# MPPT_MCU.net
KiCad netlist of a schematic drawn in Altium Designer
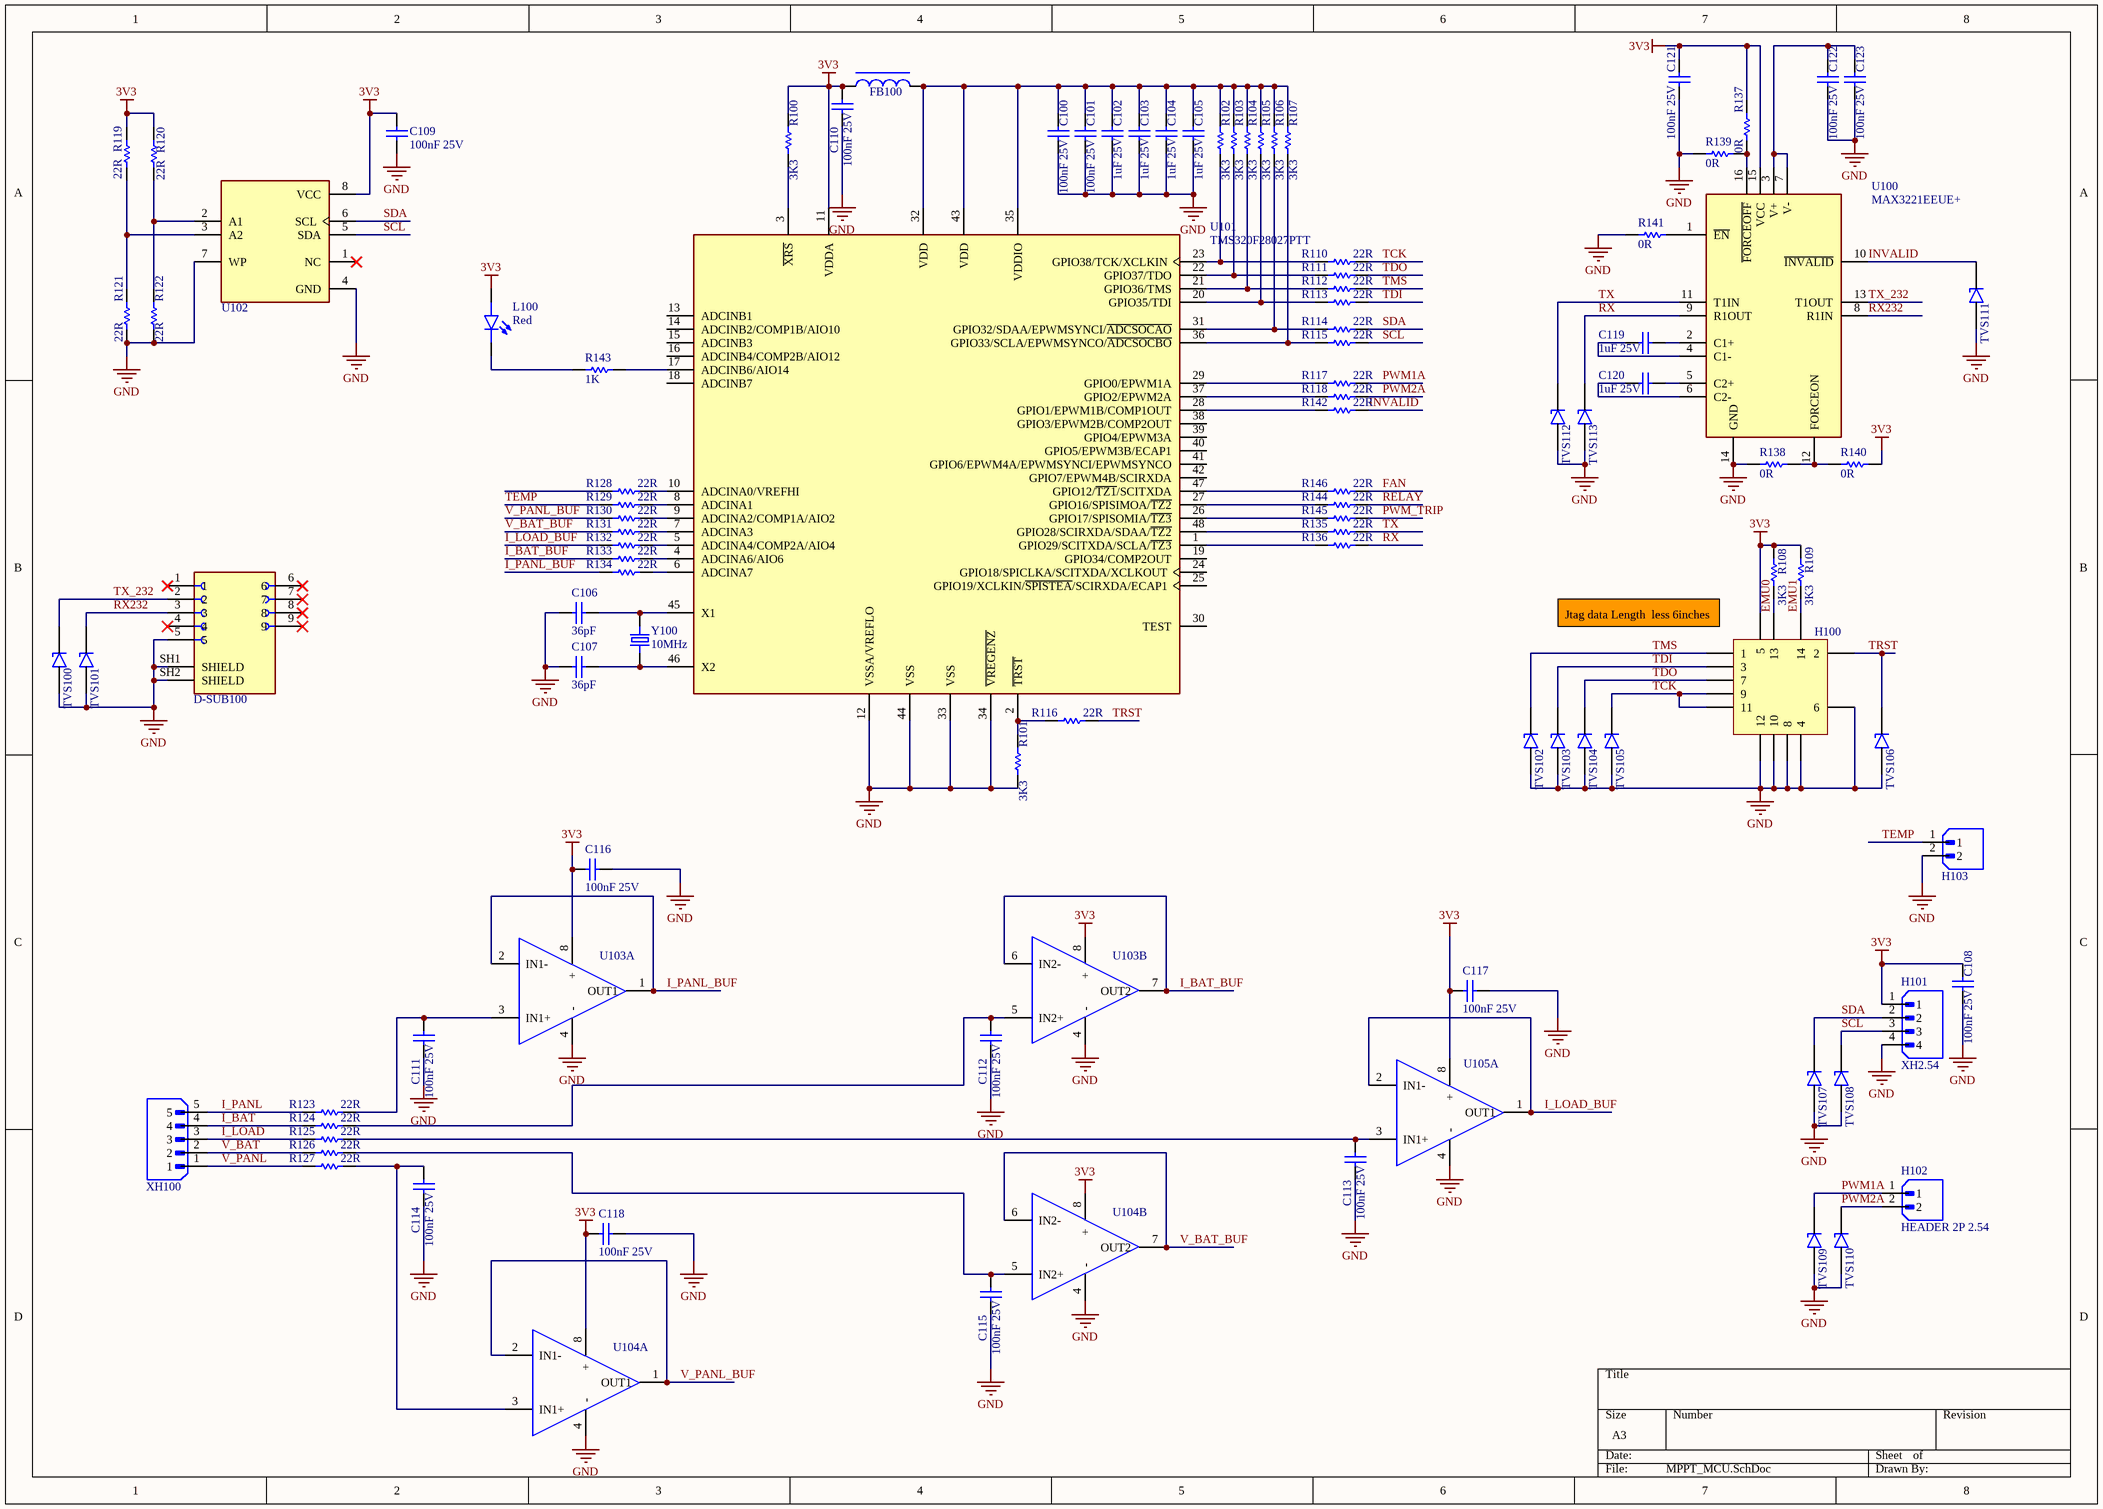
[diagram p0: MPPT_MCU.SchDoc]

(export (version "E")
  (design (tool "Eeschema 10.0.6"))
  (components
    (comp (ref "C100")
      (value "100nF 25V")
      (footprint "Cap cer 0603")
      (description "Multilayer Ceramic Capacitor, 0.1 uF, 25 V, ï¿½ 10%, X7R, 0603 [1608 Metric]")
      (fields
        (field (name "MANUFACTURER") "Murata")
        (field (name "MANUFACTURER PART NUMBER") "GCM188R71E104KA57D")
      )
      (libsource (lib "POWER_PIN_CAMERA") (part "GCM188R71E104KA57D"))
    )
    (comp (ref "C101")
      (value "100nF 25V")
      (footprint "Cap cer 0603")
      (description "Multilayer Ceramic Capacitor, 0.1 uF, 25 V, ï¿½ 10%, X7R, 0603 [1608 Metric]")
      (fields
        (field (name "MANUFACTURER") "Murata")
        (field (name "MANUFACTURER PART NUMBER") "GCM188R71E104KA57D")
      )
      (libsource (lib "POWER_PIN_CAMERA") (part "GCM188R71E104KA57D"))
    )
    (comp (ref "C102")
      (value "1uF 25V")
      (footprint "Cap cer 0603")
      (fields
        (field (name "MANUFACTURER") "Murata")
        (field (name "MANUFACTURER PART NUMBER") "GCM188R71E105KA64J")
        (field (name "TOLERANCE") "10%")
      )
      (libsource (lib "POWER_PIN_CAMERA") (part "GCM188R71E105KA64J"))
    )
    (comp (ref "C103")
      (value "1uF 25V")
      (footprint "Cap cer 0603")
      (fields
        (field (name "MANUFACTURER") "Murata")
        (field (name "MANUFACTURER PART NUMBER") "GCM188R71E105KA64J")
        (field (name "TOLERANCE") "10%")
      )
      (libsource (lib "POWER_PIN_CAMERA") (part "GCM188R71E105KA64J"))
    )
    (comp (ref "C104")
      (value "1uF 25V")
      (footprint "Cap cer 0603")
      (fields
        (field (name "MANUFACTURER") "Murata")
        (field (name "MANUFACTURER PART NUMBER") "GCM188R71E105KA64J")
        (field (name "TOLERANCE") "10%")
      )
      (libsource (lib "POWER_PIN_CAMERA") (part "GCM188R71E105KA64J"))
    )
    (comp (ref "C105")
      (value "1uF 25V")
      (footprint "Cap cer 0603")
      (fields
        (field (name "MANUFACTURER") "Murata")
        (field (name "MANUFACTURER PART NUMBER") "GCM188R71E105KA64J")
        (field (name "TOLERANCE") "10%")
      )
      (libsource (lib "POWER_PIN_CAMERA") (part "GCM188R71E105KA64J"))
    )
    (comp (ref "C106")
      (value "36pF")
      (footprint "Cap cer 0603")
      (description "Cap Ceramic 36pF 50V C0G 5% SMD 0603 125C T/R")
      (fields
        (field (name "MANUFACTURER") "Murata")
        (field (name "MANUFACTURER PART NUMBER") "GRM1885C1H360JA01D")
      )
      (libsource (lib "POWER_PIN_CAMERA") (part "GRM1885C1H360JA01D"))
    )
    (comp (ref "C107")
      (value "36pF")
      (footprint "Cap cer 0603")
      (description "Cap Ceramic 36pF 50V C0G 5% SMD 0603 125C T/R")
      (fields
        (field (name "MANUFACTURER") "Murata")
        (field (name "MANUFACTURER PART NUMBER") "GRM1885C1H360JA01D")
      )
      (libsource (lib "POWER_PIN_CAMERA") (part "GRM1885C1H360JA01D"))
    )
    (comp (ref "C108")
      (value "100nF 25V")
      (footprint "Cap cer 0603")
      (description "Multilayer Ceramic Capacitor, 0.1 uF, 25 V, ï¿½ 10%, X7R, 0603 [1608 Metric]")
      (fields
        (field (name "MANUFACTURER") "Murata")
        (field (name "MANUFACTURER PART NUMBER") "GCM188R71E104KA57D")
      )
      (libsource (lib "POWER_PIN_CAMERA") (part "GCM188R71E104KA57D"))
    )
    (comp (ref "C109")
      (value "100nF 25V")
      (footprint "Cap cer 0603")
      (description "Multilayer Ceramic Capacitor, 0.1 uF, 25 V, ï¿½ 10%, X7R, 0603 [1608 Metric]")
      (fields
        (field (name "MANUFACTURER") "Murata")
        (field (name "MANUFACTURER PART NUMBER") "GCM188R71E104KA57D")
      )
      (libsource (lib "POWER_PIN_CAMERA") (part "GCM188R71E104KA57D"))
    )
    (comp (ref "C110")
      (value "100nF 25V")
      (footprint "Cap cer 0603")
      (description "Multilayer Ceramic Capacitor, 0.1 uF, 25 V, ï¿½ 10%, X7R, 0603 [1608 Metric]")
      (fields
        (field (name "MANUFACTURER") "Murata")
        (field (name "MANUFACTURER PART NUMBER") "GCM188R71E104KA57D")
      )
      (libsource (lib "POWER_PIN_CAMERA") (part "GCM188R71E104KA57D"))
    )
    (comp (ref "C111")
      (value "100nF 25V")
      (footprint "Cap cer 0603")
      (description "Multilayer Ceramic Capacitor, 0.1 uF, 25 V, ï¿½ 10%, X7R, 0603 [1608 Metric]")
      (fields
        (field (name "MANUFACTURER") "Murata")
        (field (name "MANUFACTURER PART NUMBER") "GCM188R71E104KA57D")
      )
      (libsource (lib "POWER_PIN_CAMERA") (part "GCM188R71E104KA57D"))
    )
    (comp (ref "C112")
      (value "100nF 25V")
      (footprint "Cap cer 0603")
      (description "Multilayer Ceramic Capacitor, 0.1 uF, 25 V, ï¿½ 10%, X7R, 0603 [1608 Metric]")
      (fields
        (field (name "MANUFACTURER") "Murata")
        (field (name "MANUFACTURER PART NUMBER") "GCM188R71E104KA57D")
      )
      (libsource (lib "POWER_PIN_CAMERA") (part "GCM188R71E104KA57D"))
    )
    (comp (ref "C113")
      (value "100nF 25V")
      (footprint "Cap cer 0603")
      (description "Multilayer Ceramic Capacitor, 0.1 uF, 25 V, ï¿½ 10%, X7R, 0603 [1608 Metric]")
      (fields
        (field (name "MANUFACTURER") "Murata")
        (field (name "MANUFACTURER PART NUMBER") "GCM188R71E104KA57D")
      )
      (libsource (lib "POWER_PIN_CAMERA") (part "GCM188R71E104KA57D"))
    )
    (comp (ref "C114")
      (value "100nF 25V")
      (footprint "Cap cer 0603")
      (description "Multilayer Ceramic Capacitor, 0.1 uF, 25 V, ï¿½ 10%, X7R, 0603 [1608 Metric]")
      (fields
        (field (name "MANUFACTURER") "Murata")
        (field (name "MANUFACTURER PART NUMBER") "GCM188R71E104KA57D")
      )
      (libsource (lib "POWER_PIN_CAMERA") (part "GCM188R71E104KA57D"))
    )
    (comp (ref "C115")
      (value "100nF 25V")
      (footprint "Cap cer 0603")
      (description "Multilayer Ceramic Capacitor, 0.1 uF, 25 V, ï¿½ 10%, X7R, 0603 [1608 Metric]")
      (fields
        (field (name "MANUFACTURER") "Murata")
        (field (name "MANUFACTURER PART NUMBER") "GCM188R71E104KA57D")
      )
      (libsource (lib "POWER_PIN_CAMERA") (part "GCM188R71E104KA57D"))
    )
    (comp (ref "C116")
      (value "100nF 25V")
      (footprint "Cap cer 0603")
      (description "Multilayer Ceramic Capacitor, 0.1 uF, 25 V, ï¿½ 10%, X7R, 0603 [1608 Metric]")
      (fields
        (field (name "MANUFACTURER") "Murata")
        (field (name "MANUFACTURER PART NUMBER") "GCM188R71E104KA57D")
      )
      (libsource (lib "POWER_PIN_CAMERA") (part "GCM188R71E104KA57D"))
    )
    (comp (ref "C117")
      (value "100nF 25V")
      (footprint "Cap cer 0603")
      (description "Multilayer Ceramic Capacitor, 0.1 uF, 25 V, ï¿½ 10%, X7R, 0603 [1608 Metric]")
      (fields
        (field (name "MANUFACTURER") "Murata")
        (field (name "MANUFACTURER PART NUMBER") "GCM188R71E104KA57D")
      )
      (libsource (lib "POWER_PIN_CAMERA") (part "GCM188R71E104KA57D"))
    )
    (comp (ref "C118")
      (value "100nF 25V")
      (footprint "Cap cer 0603")
      (description "Multilayer Ceramic Capacitor, 0.1 uF, 25 V, ï¿½ 10%, X7R, 0603 [1608 Metric]")
      (fields
        (field (name "MANUFACTURER") "Murata")
        (field (name "MANUFACTURER PART NUMBER") "GCM188R71E104KA57D")
      )
      (libsource (lib "POWER_PIN_CAMERA") (part "GCM188R71E104KA57D"))
    )
    (comp (ref "C119")
      (value "1uF 25V")
      (footprint "Cap cer 0603")
      (fields
        (field (name "MANUFACTURER") "Murata")
        (field (name "MANUFACTURER PART NUMBER") "GCM188R71E105KA64J")
        (field (name "TOLERANCE") "10%")
      )
      (libsource (lib "POWER_PIN_CAMERA") (part "GCM188R71E105KA64J"))
    )
    (comp (ref "C120")
      (value "1uF 25V")
      (footprint "Cap cer 0603")
      (fields
        (field (name "MANUFACTURER") "Murata")
        (field (name "MANUFACTURER PART NUMBER") "GCM188R71E105KA64J")
        (field (name "TOLERANCE") "10%")
      )
      (libsource (lib "POWER_PIN_CAMERA") (part "GCM188R71E105KA64J"))
    )
    (comp (ref "C121")
      (value "100nF 25V")
      (footprint "Cap cer 0603")
      (description "Multilayer Ceramic Capacitor, 0.1 uF, 25 V, ï¿½ 10%, X7R, 0603 [1608 Metric]")
      (fields
        (field (name "MANUFACTURER") "Murata")
        (field (name "MANUFACTURER PART NUMBER") "GCM188R71E104KA57D")
      )
      (libsource (lib "POWER_PIN_CAMERA") (part "GCM188R71E104KA57D"))
    )
    (comp (ref "C122")
      (value "100nF 25V")
      (footprint "Cap cer 0603")
      (description "Multilayer Ceramic Capacitor, 0.1 uF, 25 V, ï¿½ 10%, X7R, 0603 [1608 Metric]")
      (fields
        (field (name "MANUFACTURER") "Murata")
        (field (name "MANUFACTURER PART NUMBER") "GCM188R71E104KA57D")
      )
      (libsource (lib "POWER_PIN_CAMERA") (part "GCM188R71E104KA57D"))
    )
    (comp (ref "C123")
      (value "100nF 25V")
      (footprint "Cap cer 0603")
      (description "Multilayer Ceramic Capacitor, 0.1 uF, 25 V, ï¿½ 10%, X7R, 0603 [1608 Metric]")
      (fields
        (field (name "MANUFACTURER") "Murata")
        (field (name "MANUFACTURER PART NUMBER") "GCM188R71E104KA57D")
      )
      (libsource (lib "POWER_PIN_CAMERA") (part "GCM188R71E104KA57D"))
    )
    (comp (ref "D-SUB100")
      (value "9PIN")
      (footprint "D-SUB")
      (description "Conn D-Subminiature SKT 9 POS 2.74mm Solder RA Thru-Hole 9 Terminal 1 Port Tray")
      (fields
        (field (name "MANUFACTURER") "TE Connectivity AMP")
        (field (name "MANUFACTURER PART NUMBER") "5747844-6")
      )
      (libsource (lib "MPPT_600W") (part "5747844-6"))
    )
    (comp (ref "FB100")
      (value "Ferrite Beads Multi-Layer 390Ohm 25% 100MHz 500mA 300mOhm DCR 0603 Automotive T/R")
      (footprint "FERRITE BEAD 0603")
      (fields
        (field (name "MANUFACTURER") "Murata")
        (field (name "MANUFACTURER PART NUMBER") "BLM18EG391TH1D")
        (field (name "TOLERANCE") "25%")
      )
      (libsource (lib "MPPT_600W") (part "Ferrite Bead"))
    )
    (comp (ref "H100")
      (value "HDR2X7 2.54mm")
      (footprint "HDR2X7")
      (libsource (lib "MPPT_600W") (part "HDR2X7"))
    )
    (comp (ref "H101")
      (value "XH2.54")
      (footprint "XH2.54")
      (description "Board Connector, 4 Contact(s), 1 Row(s), Male, Straight, Solder Terminal,")
      (fields (field (name "MANUFACTURER") "JST") (field (name "MANUFACTURER PART NUMBER") "B4B-XH-A"))
      (libsource (lib "POWER_PIN_CAMERA") (part "B4B-XH-A"))
    )
    (comp (ref "H102")
      (value "HEADER 2P 2.54")
      (footprint "HEADER 2P 2.544")
      (description "CONNECTOR HEADER, XH SERIES, 2 POSITION, 2.50MM, Press-Fit Solder, Detent Lock, Natural")
      (fields
        (field (name "MANUFACTURER") "JST")
        (field (name "MANUFACTURER PART NUMBER") "B2B-XH-A(LF)(SN)")
      )
      (libsource (lib "MPPT_600W") (part "B2B-XH-A(LF)(SN)"))
    )
    (comp (ref "H103")
      (value "HEADER 2P 2.54")
      (footprint "HEADER 2P 2.544")
      (description "CONNECTOR HEADER, XH SERIES, 2 POSITION, 2.50MM, Press-Fit Solder, Detent Lock, Natural")
      (fields
        (field (name "MANUFACTURER") "JST")
        (field (name "MANUFACTURER PART NUMBER") "B2B-XH-A(LF)(SN)")
      )
      (libsource (lib "MPPT_600W") (part "B2B-XH-A(LF)(SN)"))
    )
    (comp (ref "L100")
      (value "Red")
      (footprint "Led 0603")
      (description "LED Uni-Color Red 2-Pin Chip 0603(1608Metric) T/R")
      (fields
        (field (name "MANUFACTURER") "Dialight")
        (field (name "MANUFACTURER PART NUMBER") "597-5004-407F")
      )
      (libsource (lib "POWER_PIN_CAMERA") (part "597-5004-407F"))
    )
    (comp (ref "R100")
      (value "3K3")
      (footprint "Res 0603")
      (description "Res Thick Film 0603 10K Ohm 5% 1/10W ¦200ppm/¦C SMD Paper T/R")
      (fields
        (field (name "MANUFACTURER") "Vishay Dale")
        (field (name "MANUFACTURER PART NUMBER") "CRCW060310K0JNEA")
      )
      (libsource (lib "POWER_PIN_CAMERA") (part "Resistor 10K"))
    )
    (comp (ref "R101")
      (value "3K3")
      (footprint "Res 0603")
      (description "Res Thick Film 0603 10K Ohm 5% 1/10W ¦200ppm/¦C SMD Paper T/R")
      (fields
        (field (name "MANUFACTURER") "Vishay Dale")
        (field (name "MANUFACTURER PART NUMBER") "CRCW060310K0JNEA")
      )
      (libsource (lib "POWER_PIN_CAMERA") (part "Resistor 10K"))
    )
    (comp (ref "R102")
      (value "3K3")
      (footprint "Res 0603")
      (description "Res Thick Film 0603 10K Ohm 5% 1/10W ¦200ppm/¦C SMD Paper T/R")
      (fields
        (field (name "MANUFACTURER") "Vishay Dale")
        (field (name "MANUFACTURER PART NUMBER") "CRCW060310K0JNEA")
      )
      (libsource (lib "POWER_PIN_CAMERA") (part "Resistor 10K"))
    )
    (comp (ref "R103")
      (value "3K3")
      (footprint "Res 0603")
      (description "Res Thick Film 0603 10K Ohm 5% 1/10W ¦200ppm/¦C SMD Paper T/R")
      (fields
        (field (name "MANUFACTURER") "Vishay Dale")
        (field (name "MANUFACTURER PART NUMBER") "CRCW060310K0JNEA")
      )
      (libsource (lib "POWER_PIN_CAMERA") (part "Resistor 10K"))
    )
    (comp (ref "R104")
      (value "3K3")
      (footprint "Res 0603")
      (description "Res Thick Film 0603 10K Ohm 5% 1/10W ¦200ppm/¦C SMD Paper T/R")
      (fields
        (field (name "MANUFACTURER") "Vishay Dale")
        (field (name "MANUFACTURER PART NUMBER") "CRCW060310K0JNEA")
      )
      (libsource (lib "POWER_PIN_CAMERA") (part "Resistor 10K"))
    )
    (comp (ref "R105")
      (value "3K3")
      (footprint "Res 0603")
      (description "Res Thick Film 0603 10K Ohm 5% 1/10W ¦200ppm/¦C SMD Paper T/R")
      (fields
        (field (name "MANUFACTURER") "Vishay Dale")
        (field (name "MANUFACTURER PART NUMBER") "CRCW060310K0JNEA")
      )
      (libsource (lib "POWER_PIN_CAMERA") (part "Resistor 10K"))
    )
    (comp (ref "R106")
      (value "3K3")
      (footprint "Res 0603")
      (description "Res Thick Film 0603 10K Ohm 5% 1/10W ¦200ppm/¦C SMD Paper T/R")
      (fields
        (field (name "MANUFACTURER") "Vishay Dale")
        (field (name "MANUFACTURER PART NUMBER") "CRCW060310K0JNEA")
      )
      (libsource (lib "POWER_PIN_CAMERA") (part "Resistor 10K"))
    )
    (comp (ref "R107")
      (value "3K3")
      (footprint "Res 0603")
      (description "Res Thick Film 0603 10K Ohm 5% 1/10W ¦200ppm/¦C SMD Paper T/R")
      (fields
        (field (name "MANUFACTURER") "Vishay Dale")
        (field (name "MANUFACTURER PART NUMBER") "CRCW060310K0JNEA")
      )
      (libsource (lib "POWER_PIN_CAMERA") (part "Resistor 10K"))
    )
    (comp (ref "R108")
      (value "3K3")
      (footprint "Res 0603")
      (description "Res Thick Film 0603 10K Ohm 5% 1/10W ¦200ppm/¦C SMD Paper T/R")
      (fields
        (field (name "MANUFACTURER") "Vishay Dale")
        (field (name "MANUFACTURER PART NUMBER") "CRCW060310K0JNEA")
      )
      (libsource (lib "POWER_PIN_CAMERA") (part "Resistor 10K"))
    )
    (comp (ref "R109")
      (value "3K3")
      (footprint "Res 0603")
      (description "Res Thick Film 0603 10K Ohm 5% 1/10W ¦200ppm/¦C SMD Paper T/R")
      (fields
        (field (name "MANUFACTURER") "Vishay Dale")
        (field (name "MANUFACTURER PART NUMBER") "CRCW060310K0JNEA")
      )
      (libsource (lib "POWER_PIN_CAMERA") (part "Resistor 10K"))
    )
    (comp (ref "R110")
      (value "22R")
      (footprint "Res 0603")
      (description "Res Thick Film 0603 22 Ohm 5% 1/10W ±200ppm/°C Molded SMD SMD Paper Tape on Plastic Reel")
      (fields
        (field (name "MANUFACTURER") "Bourns")
        (field (name "MANUFACTURER PART NUMBER") "CR0603-JW-220ELF")
      )
      (libsource (lib "POWER_PIN_CAMERA") (part "Resistor 22R"))
    )
    (comp (ref "R111")
      (value "22R")
      (footprint "Res 0603")
      (description "Res Thick Film 0603 22 Ohm 5% 1/10W ±200ppm/°C Molded SMD SMD Paper Tape on Plastic Reel")
      (fields
        (field (name "MANUFACTURER") "Bourns")
        (field (name "MANUFACTURER PART NUMBER") "CR0603-JW-220ELF")
      )
      (libsource (lib "POWER_PIN_CAMERA") (part "Resistor 22R"))
    )
    (comp (ref "R112")
      (value "22R")
      (footprint "Res 0603")
      (description "Res Thick Film 0603 22 Ohm 5% 1/10W ±200ppm/°C Molded SMD SMD Paper Tape on Plastic Reel")
      (fields
        (field (name "MANUFACTURER") "Bourns")
        (field (name "MANUFACTURER PART NUMBER") "CR0603-JW-220ELF")
      )
      (libsource (lib "POWER_PIN_CAMERA") (part "Resistor 22R"))
    )
    (comp (ref "R113")
      (value "22R")
      (footprint "Res 0603")
      (description "Res Thick Film 0603 22 Ohm 5% 1/10W ±200ppm/°C Molded SMD SMD Paper Tape on Plastic Reel")
      (fields
        (field (name "MANUFACTURER") "Bourns")
        (field (name "MANUFACTURER PART NUMBER") "CR0603-JW-220ELF")
      )
      (libsource (lib "POWER_PIN_CAMERA") (part "Resistor 22R"))
    )
    (comp (ref "R114")
      (value "22R")
      (footprint "Res 0603")
      (description "Res Thick Film 0603 22 Ohm 5% 1/10W ±200ppm/°C Molded SMD SMD Paper Tape on Plastic Reel")
      (fields
        (field (name "MANUFACTURER") "Bourns")
        (field (name "MANUFACTURER PART NUMBER") "CR0603-JW-220ELF")
      )
      (libsource (lib "POWER_PIN_CAMERA") (part "Resistor 22R"))
    )
    (comp (ref "R115")
      (value "22R")
      (footprint "Res 0603")
      (description "Res Thick Film 0603 22 Ohm 5% 1/10W ±200ppm/°C Molded SMD SMD Paper Tape on Plastic Reel")
      (fields
        (field (name "MANUFACTURER") "Bourns")
        (field (name "MANUFACTURER PART NUMBER") "CR0603-JW-220ELF")
      )
      (libsource (lib "POWER_PIN_CAMERA") (part "Resistor 22R"))
    )
    (comp (ref "R116")
      (value "22R")
      (footprint "Res 0603")
      (description "Res Thick Film 0603 22 Ohm 5% 1/10W ±200ppm/°C Molded SMD SMD Paper Tape on Plastic Reel")
      (fields
        (field (name "MANUFACTURER") "Bourns")
        (field (name "MANUFACTURER PART NUMBER") "CR0603-JW-220ELF")
      )
      (libsource (lib "POWER_PIN_CAMERA") (part "Resistor 22R"))
    )
    (comp (ref "R117")
      (value "22R")
      (footprint "Res 0603")
      (description "Res Thick Film 0603 22 Ohm 5% 1/10W ±200ppm/°C Molded SMD SMD Paper Tape on Plastic Reel")
      (fields
        (field (name "MANUFACTURER") "Bourns")
        (field (name "MANUFACTURER PART NUMBER") "CR0603-JW-220ELF")
      )
      (libsource (lib "POWER_PIN_CAMERA") (part "Resistor 22R"))
    )
    (comp (ref "R118")
      (value "22R")
      (footprint "Res 0603")
      (description "Res Thick Film 0603 22 Ohm 5% 1/10W ±200ppm/°C Molded SMD SMD Paper Tape on Plastic Reel")
      (fields
        (field (name "MANUFACTURER") "Bourns")
        (field (name "MANUFACTURER PART NUMBER") "CR0603-JW-220ELF")
      )
      (libsource (lib "POWER_PIN_CAMERA") (part "Resistor 22R"))
    )
    (comp (ref "R119")
      (value "22R")
      (footprint "Res 0603")
      (description "Res Thick Film 0603 22 Ohm 5% 1/10W ±200ppm/°C Molded SMD SMD Paper Tape on Plastic Reel")
      (fields
        (field (name "MANUFACTURER") "Bourns")
        (field (name "MANUFACTURER PART NUMBER") "CR0603-JW-220ELF")
      )
      (libsource (lib "POWER_PIN_CAMERA") (part "Resistor 22R"))
    )
    (comp (ref "R120")
      (value "22R")
      (footprint "Res 0603")
      (description "Res Thick Film 0603 22 Ohm 5% 1/10W ±200ppm/°C Molded SMD SMD Paper Tape on Plastic Reel")
      (fields
        (field (name "MANUFACTURER") "Bourns")
        (field (name "MANUFACTURER PART NUMBER") "CR0603-JW-220ELF")
      )
      (libsource (lib "POWER_PIN_CAMERA") (part "Resistor 22R"))
    )
    (comp (ref "R121")
      (value "22R")
      (footprint "Res 0603")
      (description "Res Thick Film 0603 22 Ohm 5% 1/10W ±200ppm/°C Molded SMD SMD Paper Tape on Plastic Reel")
      (fields
        (field (name "MANUFACTURER") "Bourns")
        (field (name "MANUFACTURER PART NUMBER") "CR0603-JW-220ELF")
      )
      (libsource (lib "POWER_PIN_CAMERA") (part "Resistor 22R"))
    )
    (comp (ref "R122")
      (value "22R")
      (footprint "Res 0603")
      (description "Res Thick Film 0603 22 Ohm 5% 1/10W ±200ppm/°C Molded SMD SMD Paper Tape on Plastic Reel")
      (fields
        (field (name "MANUFACTURER") "Bourns")
        (field (name "MANUFACTURER PART NUMBER") "CR0603-JW-220ELF")
      )
      (libsource (lib "POWER_PIN_CAMERA") (part "Resistor 22R"))
    )
    (comp (ref "R123")
      (value "22R")
      (footprint "Res 0603")
      (description "Res Thick Film 0603 22 Ohm 5% 1/10W ±200ppm/°C Molded SMD SMD Paper Tape on Plastic Reel")
      (fields
        (field (name "MANUFACTURER") "Bourns")
        (field (name "MANUFACTURER PART NUMBER") "CR0603-JW-220ELF")
      )
      (libsource (lib "POWER_PIN_CAMERA") (part "Resistor 22R"))
    )
    (comp (ref "R124")
      (value "22R")
      (footprint "Res 0603")
      (description "Res Thick Film 0603 22 Ohm 5% 1/10W ±200ppm/°C Molded SMD SMD Paper Tape on Plastic Reel")
      (fields
        (field (name "MANUFACTURER") "Bourns")
        (field (name "MANUFACTURER PART NUMBER") "CR0603-JW-220ELF")
      )
      (libsource (lib "POWER_PIN_CAMERA") (part "Resistor 22R"))
    )
    (comp (ref "R125")
      (value "22R")
      (footprint "Res 0603")
      (description "Res Thick Film 0603 22 Ohm 5% 1/10W ±200ppm/°C Molded SMD SMD Paper Tape on Plastic Reel")
      (fields
        (field (name "MANUFACTURER") "Bourns")
        (field (name "MANUFACTURER PART NUMBER") "CR0603-JW-220ELF")
      )
      (libsource (lib "POWER_PIN_CAMERA") (part "Resistor 22R"))
    )
    (comp (ref "R126")
      (value "22R")
      (footprint "Res 0603")
      (description "Res Thick Film 0603 22 Ohm 5% 1/10W ±200ppm/°C Molded SMD SMD Paper Tape on Plastic Reel")
      (fields
        (field (name "MANUFACTURER") "Bourns")
        (field (name "MANUFACTURER PART NUMBER") "CR0603-JW-220ELF")
      )
      (libsource (lib "POWER_PIN_CAMERA") (part "Resistor 22R"))
    )
    (comp (ref "R127")
      (value "22R")
      (footprint "Res 0603")
      (description "Res Thick Film 0603 22 Ohm 5% 1/10W ±200ppm/°C Molded SMD SMD Paper Tape on Plastic Reel")
      (fields
        (field (name "MANUFACTURER") "Bourns")
        (field (name "MANUFACTURER PART NUMBER") "CR0603-JW-220ELF")
      )
      (libsource (lib "POWER_PIN_CAMERA") (part "Resistor 22R"))
    )
    (comp (ref "R128")
      (value "22R")
      (footprint "Res 0603")
      (description "Res Thick Film 0603 22 Ohm 5% 1/10W ±200ppm/°C Molded SMD SMD Paper Tape on Plastic Reel")
      (fields
        (field (name "MANUFACTURER") "Bourns")
        (field (name "MANUFACTURER PART NUMBER") "CR0603-JW-220ELF")
      )
      (libsource (lib "POWER_PIN_CAMERA") (part "Resistor 22R"))
    )
    (comp (ref "R129")
      (value "22R")
      (footprint "Res 0603")
      (description "Res Thick Film 0603 22 Ohm 5% 1/10W ±200ppm/°C Molded SMD SMD Paper Tape on Plastic Reel")
      (fields
        (field (name "MANUFACTURER") "Bourns")
        (field (name "MANUFACTURER PART NUMBER") "CR0603-JW-220ELF")
      )
      (libsource (lib "POWER_PIN_CAMERA") (part "Resistor 22R"))
    )
    (comp (ref "R130")
      (value "22R")
      (footprint "Res 0603")
      (description "Res Thick Film 0603 22 Ohm 5% 1/10W ±200ppm/°C Molded SMD SMD Paper Tape on Plastic Reel")
      (fields
        (field (name "MANUFACTURER") "Bourns")
        (field (name "MANUFACTURER PART NUMBER") "CR0603-JW-220ELF")
      )
      (libsource (lib "POWER_PIN_CAMERA") (part "Resistor 22R"))
    )
    (comp (ref "R131")
      (value "22R")
      (footprint "Res 0603")
      (description "Res Thick Film 0603 22 Ohm 5% 1/10W ±200ppm/°C Molded SMD SMD Paper Tape on Plastic Reel")
      (fields
        (field (name "MANUFACTURER") "Bourns")
        (field (name "MANUFACTURER PART NUMBER") "CR0603-JW-220ELF")
      )
      (libsource (lib "POWER_PIN_CAMERA") (part "Resistor 22R"))
    )
    (comp (ref "R132")
      (value "22R")
      (footprint "Res 0603")
      (description "Res Thick Film 0603 22 Ohm 5% 1/10W ±200ppm/°C Molded SMD SMD Paper Tape on Plastic Reel")
      (fields
        (field (name "MANUFACTURER") "Bourns")
        (field (name "MANUFACTURER PART NUMBER") "CR0603-JW-220ELF")
      )
      (libsource (lib "POWER_PIN_CAMERA") (part "Resistor 22R"))
    )
    (comp (ref "R133")
      (value "22R")
      (footprint "Res 0603")
      (description "Res Thick Film 0603 22 Ohm 5% 1/10W ±200ppm/°C Molded SMD SMD Paper Tape on Plastic Reel")
      (fields
        (field (name "MANUFACTURER") "Bourns")
        (field (name "MANUFACTURER PART NUMBER") "CR0603-JW-220ELF")
      )
      (libsource (lib "POWER_PIN_CAMERA") (part "Resistor 22R"))
    )
    (comp (ref "R134")
      (value "22R")
      (footprint "Res 0603")
      (description "Res Thick Film 0603 22 Ohm 5% 1/10W ±200ppm/°C Molded SMD SMD Paper Tape on Plastic Reel")
      (fields
        (field (name "MANUFACTURER") "Bourns")
        (field (name "MANUFACTURER PART NUMBER") "CR0603-JW-220ELF")
      )
      (libsource (lib "POWER_PIN_CAMERA") (part "Resistor 22R"))
    )
    (comp (ref "R135")
      (value "22R")
      (footprint "Res 0603")
      (description "Res Thick Film 0603 22 Ohm 5% 1/10W ±200ppm/°C Molded SMD SMD Paper Tape on Plastic Reel")
      (fields
        (field (name "MANUFACTURER") "Bourns")
        (field (name "MANUFACTURER PART NUMBER") "CR0603-JW-220ELF")
      )
      (libsource (lib "POWER_PIN_CAMERA") (part "Resistor 22R"))
    )
    (comp (ref "R136")
      (value "22R")
      (footprint "Res 0603")
      (description "Res Thick Film 0603 22 Ohm 5% 1/10W ±200ppm/°C Molded SMD SMD Paper Tape on Plastic Reel")
      (fields
        (field (name "MANUFACTURER") "Bourns")
        (field (name "MANUFACTURER PART NUMBER") "CR0603-JW-220ELF")
      )
      (libsource (lib "POWER_PIN_CAMERA") (part "Resistor 22R"))
    )
    (comp (ref "R137")
      (value "0R")
      (footprint "Res 0603")
      (description "Res Thick Film 0603 22 Ohm 5% 1/10W ±200ppm/°C Molded SMD SMD Paper Tape on Plastic Reel")
      (fields
        (field (name "MANUFACTURER") "Bourns")
        (field (name "MANUFACTURER PART NUMBER") "CR0603-JW-220ELF")
      )
      (libsource (lib "POWER_PIN_CAMERA") (part "Resistor 22R"))
    )
    (comp (ref "R138")
      (value "0R")
      (footprint "Res 0603")
      (description "Res Thick Film 0603 22 Ohm 5% 1/10W ±200ppm/°C Molded SMD SMD Paper Tape on Plastic Reel")
      (fields
        (field (name "MANUFACTURER") "Bourns")
        (field (name "MANUFACTURER PART NUMBER") "CR0603-JW-220ELF")
      )
      (libsource (lib "POWER_PIN_CAMERA") (part "Resistor 22R"))
    )
    (comp (ref "R139")
      (value "0R")
      (footprint "Res 0603")
      (description "Res Thick Film 0603 22 Ohm 5% 1/10W ±200ppm/°C Molded SMD SMD Paper Tape on Plastic Reel")
      (fields
        (field (name "MANUFACTURER") "Bourns")
        (field (name "MANUFACTURER PART NUMBER") "CR0603-JW-220ELF")
      )
      (libsource (lib "POWER_PIN_CAMERA") (part "Resistor 22R"))
    )
    (comp (ref "R140")
      (value "0R")
      (footprint "Res 0603")
      (description "Res Thick Film 0603 22 Ohm 5% 1/10W ±200ppm/°C Molded SMD SMD Paper Tape on Plastic Reel")
      (fields
        (field (name "MANUFACTURER") "Bourns")
        (field (name "MANUFACTURER PART NUMBER") "CR0603-JW-220ELF")
      )
      (libsource (lib "POWER_PIN_CAMERA") (part "Resistor 22R"))
    )
    (comp (ref "R141")
      (value "0R")
      (footprint "Res 0603")
      (description "Res Thick Film 0603 22 Ohm 5% 1/10W ±200ppm/°C Molded SMD SMD Paper Tape on Plastic Reel")
      (fields
        (field (name "MANUFACTURER") "Bourns")
        (field (name "MANUFACTURER PART NUMBER") "CR0603-JW-220ELF")
      )
      (libsource (lib "POWER_PIN_CAMERA") (part "Resistor 22R"))
    )
    (comp (ref "R142")
      (value "22R")
      (footprint "Res 0603")
      (description "Res Thick Film 0603 22 Ohm 5% 1/10W ±200ppm/°C Molded SMD SMD Paper Tape on Plastic Reel")
      (fields
        (field (name "MANUFACTURER") "Bourns")
        (field (name "MANUFACTURER PART NUMBER") "CR0603-JW-220ELF")
      )
      (libsource (lib "POWER_PIN_CAMERA") (part "Resistor 22R"))
    )
    (comp (ref "R143")
      (value "1K")
      (footprint "Res 0603")
      (description "Res Thick Film 0603 2.2K Ohm 5% 1/10W ±200ppm/°C Molded SMD SMD Paper T/R")
      (fields
        (field (name "MANUFACTURER") "Vishay")
        (field (name "MANUFACTURER PART NUMBER") "CRCW06032K20JNEA")
      )
      (libsource (lib "POWER_PIN_CAMERA") (part "Resistor 2.2K"))
    )
    (comp (ref "R144")
      (value "22R")
      (footprint "Res 0603")
      (description "Res Thick Film 0603 22 Ohm 5% 1/10W ±200ppm/°C Molded SMD SMD Paper Tape on Plastic Reel")
      (fields
        (field (name "MANUFACTURER") "Bourns")
        (field (name "MANUFACTURER PART NUMBER") "CR0603-JW-220ELF")
      )
      (libsource (lib "POWER_PIN_CAMERA") (part "Resistor 22R"))
    )
    (comp (ref "R145")
      (value "22R")
      (footprint "Res 0603")
      (description "Res Thick Film 0603 22 Ohm 5% 1/10W ±200ppm/°C Molded SMD SMD Paper Tape on Plastic Reel")
      (fields
        (field (name "MANUFACTURER") "Bourns")
        (field (name "MANUFACTURER PART NUMBER") "CR0603-JW-220ELF")
      )
      (libsource (lib "POWER_PIN_CAMERA") (part "Resistor 22R"))
    )
    (comp (ref "R146")
      (value "22R")
      (footprint "Res 0603")
      (description "Res Thick Film 0603 22 Ohm 5% 1/10W ±200ppm/°C Molded SMD SMD Paper Tape on Plastic Reel")
      (fields
        (field (name "MANUFACTURER") "Bourns")
        (field (name "MANUFACTURER PART NUMBER") "CR0603-JW-220ELF")
      )
      (libsource (lib "POWER_PIN_CAMERA") (part "Resistor 22R"))
    )
    (comp (ref "TVS100")
      (value "SMCJ5.0A-13-F")
      (footprint "TVS 5V")
      (description "SMCJ5.0A Series 1500 W 5.0 V Surface Mount Uni-Directional TVS Diode - DO-214AB")
      (fields (field (name "MANUFACTURER") "Diodes"))
      (libsource (lib "MPPT_600W") (part "SMCJ5.0A-13-F"))
    )
    (comp (ref "TVS101")
      (value "SMCJ5.0A-13-F")
      (footprint "TVS 5V")
      (description "SMCJ5.0A Series 1500 W 5.0 V Surface Mount Uni-Directional TVS Diode - DO-214AB")
      (fields (field (name "MANUFACTURER") "Diodes"))
      (libsource (lib "MPPT_600W") (part "SMCJ5.0A-13-F"))
    )
    (comp (ref "TVS102")
      (value "SMCJ5.0A-13-F")
      (footprint "TVS 5V")
      (description "SMCJ5.0A Series 1500 W 5.0 V Surface Mount Uni-Directional TVS Diode - DO-214AB")
      (fields (field (name "MANUFACTURER") "Diodes"))
      (libsource (lib "MPPT_600W") (part "SMCJ5.0A-13-F"))
    )
    (comp (ref "TVS103")
      (value "SMCJ5.0A-13-F")
      (footprint "TVS 5V")
      (description "SMCJ5.0A Series 1500 W 5.0 V Surface Mount Uni-Directional TVS Diode - DO-214AB")
      (fields (field (name "MANUFACTURER") "Diodes"))
      (libsource (lib "MPPT_600W") (part "SMCJ5.0A-13-F"))
    )
    (comp (ref "TVS104")
      (value "SMCJ5.0A-13-F")
      (footprint "TVS 5V")
      (description "SMCJ5.0A Series 1500 W 5.0 V Surface Mount Uni-Directional TVS Diode - DO-214AB")
      (fields (field (name "MANUFACTURER") "Diodes"))
      (libsource (lib "MPPT_600W") (part "SMCJ5.0A-13-F"))
    )
    (comp (ref "TVS105")
      (value "SMCJ5.0A-13-F")
      (footprint "TVS 5V")
      (description "SMCJ5.0A Series 1500 W 5.0 V Surface Mount Uni-Directional TVS Diode - DO-214AB")
      (fields (field (name "MANUFACTURER") "Diodes"))
      (libsource (lib "MPPT_600W") (part "SMCJ5.0A-13-F"))
    )
    (comp (ref "TVS106")
      (value "SMCJ5.0A-13-F")
      (footprint "TVS 5V")
      (description "SMCJ5.0A Series 1500 W 5.0 V Surface Mount Uni-Directional TVS Diode - DO-214AB")
      (fields (field (name "MANUFACTURER") "Diodes"))
      (libsource (lib "MPPT_600W") (part "SMCJ5.0A-13-F"))
    )
    (comp (ref "TVS107")
      (value "SMCJ5.0A-13-F")
      (footprint "TVS 5V")
      (description "SMCJ5.0A Series 1500 W 5.0 V Surface Mount Uni-Directional TVS Diode - DO-214AB")
      (fields (field (name "MANUFACTURER") "Diodes"))
      (libsource (lib "MPPT_600W") (part "SMCJ5.0A-13-F"))
    )
    (comp (ref "TVS108")
      (value "SMCJ5.0A-13-F")
      (footprint "TVS 5V")
      (description "SMCJ5.0A Series 1500 W 5.0 V Surface Mount Uni-Directional TVS Diode - DO-214AB")
      (fields (field (name "MANUFACTURER") "Diodes"))
      (libsource (lib "MPPT_600W") (part "SMCJ5.0A-13-F"))
    )
    (comp (ref "TVS109")
      (value "SMCJ5.0A-13-F")
      (footprint "TVS 5V")
      (description "SMCJ5.0A Series 1500 W 5.0 V Surface Mount Uni-Directional TVS Diode - DO-214AB")
      (fields (field (name "MANUFACTURER") "Diodes"))
      (libsource (lib "MPPT_600W") (part "SMCJ5.0A-13-F"))
    )
    (comp (ref "TVS110")
      (value "SMCJ5.0A-13-F")
      (footprint "TVS 5V")
      (description "SMCJ5.0A Series 1500 W 5.0 V Surface Mount Uni-Directional TVS Diode - DO-214AB")
      (fields (field (name "MANUFACTURER") "Diodes"))
      (libsource (lib "MPPT_600W") (part "SMCJ5.0A-13-F"))
    )
    (comp (ref "TVS111")
      (value "SMCJ5.0A-13-F")
      (footprint "TVS 5V")
      (description "SMCJ5.0A Series 1500 W 5.0 V Surface Mount Uni-Directional TVS Diode - DO-214AB")
      (fields (field (name "MANUFACTURER") "Diodes"))
      (libsource (lib "MPPT_600W") (part "SMCJ5.0A-13-F"))
    )
    (comp (ref "TVS112")
      (value "SMCJ5.0A-13-F")
      (footprint "TVS 5V")
      (description "SMCJ5.0A Series 1500 W 5.0 V Surface Mount Uni-Directional TVS Diode - DO-214AB")
      (fields (field (name "MANUFACTURER") "Diodes"))
      (libsource (lib "MPPT_600W") (part "SMCJ5.0A-13-F"))
    )
    (comp (ref "TVS113")
      (value "SMCJ5.0A-13-F")
      (footprint "TVS 5V")
      (description "SMCJ5.0A Series 1500 W 5.0 V Surface Mount Uni-Directional TVS Diode - DO-214AB")
      (fields (field (name "MANUFACTURER") "Diodes"))
      (libsource (lib "MPPT_600W") (part "SMCJ5.0A-13-F"))
    )
    (comp (ref "U100")
      (value "MAX3221EEUE+")
      (footprint "max3221")
      (description "MAX3221 Series 250 kbps 5.5V Surface Mount RS-232 Transceiver - TSSOP-16")
      (fields (field (name "MANUFACTURER") "Maxim"))
      (libsource (lib "MPPT_600W") (part "MAX3221EEUE+"))
    )
    (comp (ref "U101")
      (value "TMS320F28027PTT")
      (footprint "TMS320F28027PTT")
      (description "C2000™ 32-bit MCU with 60 MHz, 64 KB flash 48-LQFP -40 to 105")
      (fields (field (name "MANUFACTURER") "Maxim") (field (name "MANUFACTURER PART NUMBER") "MAX3221EEUE+"))
      (libsource (lib "MPPT_600W") (part "TMS320F28027PTT"))
    )
    (comp (ref "U102")
      (value "AT24C04D-SSHM-B")
      (footprint "AT24C04D")
      (description "AT24C04D Series 4 Kb (512 x 8) 1.7 V SMT I2C Compatible Serial EEPROM - SOIC-8")
      (fields (field (name "MANUFACTURER") "Microchip"))
      (libsource (lib "MPPT_600W") (part "AT24C04D-SSHM-B"))
    )
    (comp (ref "U103")
      (value "LM358DT")
      (footprint "LM358")
      (description "Operational Amplifier, 2-Channels, 1.1 MHz, 0.6 V/us, 3 V to 30 V, 8 Pins, SOIC")
      (fields (field (name "MANUFACTURER") "STMicroelectronics"))
      (libsource (lib "MPPT_600W") (part "LM358DT"))
    )
    (comp (ref "U104")
      (value "LM358DT")
      (footprint "LM358")
      (description "Operational Amplifier, 2-Channels, 1.1 MHz, 0.6 V/us, 3 V to 30 V, 8 Pins, SOIC")
      (fields (field (name "MANUFACTURER") "STMicroelectronics"))
      (libsource (lib "MPPT_600W") (part "LM358DT"))
    )
    (comp (ref "U105")
      (value "LM358DT")
      (footprint "LM358")
      (description "Operational Amplifier, 2-Channels, 1.1 MHz, 0.6 V/us, 3 V to 30 V, 8 Pins, SOIC")
      (fields (field (name "MANUFACTURER") "STMicroelectronics"))
      (libsource (lib "MPPT_600W") (part "LM358DT"))
    )
    (comp (ref "XH100")
      (value "B5B-XH-A(LF)(SN)")
      (footprint "XH2.54 5p")
      (description "Connector Header, XH Series, 5 Position, 2.50mm, Through Hole, Press-Fit, Solder, Natural")
      (fields (field (name "MANUFACTURER") "JST"))
      (libsource (lib "MPPT_600W") (part "B5B-XH-A(LF)(SN)"))
    )
    (comp (ref "Y100")
      (value "10MHz")
      (footprint "Crystal 10Mhz")
      (description "10 MHz ±20ppm Crystal 18pF 50 Ohms HC-49/US")
      (libsource (lib "MPPT_600W") (part "Crystal 10MHz"))
    )
  )
  (nets
    (net (code "1") (name "/EMU0") (class "Default")
      (node (ref "H100") (pin "13") (pinfunction "13_13") (pintype "passive"))
      (node (ref "R108") (pin "1") (pinfunction "1_1") (pintype "passive"))
    )
    (net (code "2") (name "/EMU1") (class "Default")
      (node (ref "H100") (pin "14") (pinfunction "14_14") (pintype "passive"))
      (node (ref "R109") (pin "1") (pinfunction "1_1") (pintype "passive"))
    )
    (net (code "3") (name "/FAN") (class "Default")
      (node (ref "R146") (pin "2") (pinfunction "2_2") (pintype "passive"))
    )
    (net (code "4") (name "/INVALID") (class "Default")
      (node (ref "R142") (pin "2") (pinfunction "2_2") (pintype "passive"))
      (node (ref "TVS111") (pin "1") (pinfunction "C_1") (pintype "passive"))
      (node (ref "U100") (pin "10") (pinfunction "~{INVALID}_10") (pintype "passive"))
    )
    (net (code "5") (name "/I_BAT") (class "Default")
      (node (ref "R124") (pin "1") (pinfunction "1_1") (pintype "passive"))
      (node (ref "XH100") (pin "4") (pinfunction "4_4") (pintype "passive"))
    )
    (net (code "6") (name "/I_BAT_BUF") (class "Default")
      (node (ref "R133") (pin "1") (pinfunction "1_1") (pintype "passive"))
      (node (ref "U103") (pin "6") (pinfunction "IN2-_6") (pintype "passive"))
      (node (ref "U103") (pin "7") (pinfunction "OUT2_7") (pintype "passive"))
    )
    (net (code "7") (name "/I_LOAD") (class "Default")
      (node (ref "R125") (pin "1") (pinfunction "1_1") (pintype "passive"))
      (node (ref "XH100") (pin "3") (pinfunction "3_3") (pintype "passive"))
    )
    (net (code "8") (name "/I_LOAD_BUF") (class "Default")
      (node (ref "R132") (pin "1") (pinfunction "1_1") (pintype "passive"))
      (node (ref "U105") (pin "1") (pinfunction "OUT1_1") (pintype "passive"))
      (node (ref "U105") (pin "2") (pinfunction "IN1-_2") (pintype "passive"))
    )
    (net (code "9") (name "/I_PANL") (class "Default")
      (node (ref "R123") (pin "1") (pinfunction "1_1") (pintype "passive"))
      (node (ref "XH100") (pin "5") (pinfunction "5_5") (pintype "passive"))
    )
    (net (code "10") (name "/I_PANL_BUF") (class "Default")
      (node (ref "R134") (pin "1") (pinfunction "1_1") (pintype "passive"))
      (node (ref "U103") (pin "1") (pinfunction "OUT1_1") (pintype "passive"))
      (node (ref "U103") (pin "2") (pinfunction "IN1-_2") (pintype "passive"))
    )
    (net (code "11") (name "/PWM1A") (class "Default")
      (node (ref "H102") (pin "1") (pinfunction "1_1") (pintype "passive"))
      (node (ref "R117") (pin "2") (pinfunction "2_2") (pintype "passive"))
      (node (ref "TVS109") (pin "1") (pinfunction "C_1") (pintype "passive"))
    )
    (net (code "12") (name "/PWM2A") (class "Default")
      (node (ref "H102") (pin "2") (pinfunction "2_2") (pintype "passive"))
      (node (ref "R118") (pin "2") (pinfunction "2_2") (pintype "passive"))
      (node (ref "TVS110") (pin "1") (pinfunction "C_1") (pintype "passive"))
    )
    (net (code "13") (name "/PWM_TRIP") (class "Default")
      (node (ref "R145") (pin "2") (pinfunction "2_2") (pintype "passive"))
    )
    (net (code "14") (name "/RELAY") (class "Default")
      (node (ref "R144") (pin "2") (pinfunction "2_2") (pintype "passive"))
    )
    (net (code "15") (name "/RX") (class "Default")
      (node (ref "R136") (pin "2") (pinfunction "2_2") (pintype "passive"))
      (node (ref "TVS113") (pin "1") (pinfunction "C_1") (pintype "passive"))
      (node (ref "U100") (pin "9") (pinfunction "R1OUT_9") (pintype "passive"))
    )
    (net (code "16") (name "/RX232") (class "Default")
      (node (ref "D-SUB100") (pin "3") (pinfunction "3_3") (pintype "passive"))
      (node (ref "TVS101") (pin "1") (pinfunction "C_1") (pintype "passive"))
      (node (ref "U100") (pin "8") (pinfunction "R1IN_8") (pintype "passive"))
    )
    (net (code "17") (name "/SCL") (class "Default")
      (node (ref "H101") (pin "3") (pinfunction "3_3") (pintype "passive"))
      (node (ref "R115") (pin "2") (pinfunction "2_2") (pintype "passive"))
      (node (ref "TVS108") (pin "1") (pinfunction "C_1") (pintype "passive"))
      (node (ref "U102") (pin "5") (pinfunction "SDA_5") (pintype "passive"))
    )
    (net (code "18") (name "/SDA") (class "Default")
      (node (ref "H101") (pin "2") (pinfunction "2_2") (pintype "passive"))
      (node (ref "R114") (pin "2") (pinfunction "2_2") (pintype "passive"))
      (node (ref "TVS107") (pin "1") (pinfunction "C_1") (pintype "passive"))
      (node (ref "U102") (pin "6") (pinfunction "SCL_6") (pintype "passive"))
    )
    (net (code "19") (name "/TCK") (class "Default")
      (node (ref "H100") (pin "11") (pinfunction "11_11") (pintype "passive"))
      (node (ref "H100") (pin "9") (pinfunction "9_9") (pintype "passive"))
      (node (ref "R110") (pin "2") (pinfunction "2_2") (pintype "passive"))
      (node (ref "TVS105") (pin "1") (pinfunction "C_1") (pintype "passive"))
    )
    (net (code "20") (name "/TDI") (class "Default")
      (node (ref "H100") (pin "3") (pinfunction "3_3") (pintype "passive"))
      (node (ref "R113") (pin "2") (pinfunction "2_2") (pintype "passive"))
      (node (ref "TVS103") (pin "1") (pinfunction "C_1") (pintype "passive"))
    )
    (net (code "21") (name "/TDO") (class "Default")
      (node (ref "H100") (pin "7") (pinfunction "7_7") (pintype "passive"))
      (node (ref "R111") (pin "2") (pinfunction "2_2") (pintype "passive"))
      (node (ref "TVS104") (pin "1") (pinfunction "C_1") (pintype "passive"))
    )
    (net (code "22") (name "/TEMP") (class "Default")
      (node (ref "H103") (pin "1") (pinfunction "1_1") (pintype "passive"))
      (node (ref "R129") (pin "1") (pinfunction "1_1") (pintype "passive"))
    )
    (net (code "23") (name "/TMS") (class "Default")
      (node (ref "H100") (pin "1") (pinfunction "1_1") (pintype "passive"))
      (node (ref "R112") (pin "2") (pinfunction "2_2") (pintype "passive"))
      (node (ref "TVS102") (pin "1") (pinfunction "C_1") (pintype "passive"))
    )
    (net (code "24") (name "/TRST") (class "Default")
      (node (ref "H100") (pin "2") (pinfunction "2_2") (pintype "passive"))
      (node (ref "R116") (pin "2") (pinfunction "2_2") (pintype "passive"))
      (node (ref "TVS106") (pin "1") (pinfunction "C_1") (pintype "passive"))
    )
    (net (code "25") (name "/TX") (class "Default")
      (node (ref "R135") (pin "2") (pinfunction "2_2") (pintype "passive"))
      (node (ref "TVS112") (pin "1") (pinfunction "C_1") (pintype "passive"))
      (node (ref "U100") (pin "11") (pinfunction "T1IN_11") (pintype "passive"))
    )
    (net (code "26") (name "/TX_232") (class "Default")
      (node (ref "D-SUB100") (pin "2") (pinfunction "2_2") (pintype "passive"))
      (node (ref "TVS100") (pin "1") (pinfunction "C_1") (pintype "passive"))
      (node (ref "U100") (pin "13") (pinfunction "T1OUT_13") (pintype "passive"))
    )
    (net (code "27") (name "/V_BAT") (class "Default")
      (node (ref "R126") (pin "1") (pinfunction "1_1") (pintype "passive"))
      (node (ref "XH100") (pin "2") (pinfunction "2_2") (pintype "passive"))
    )
    (net (code "28") (name "/V_BAT_BUF") (class "Default")
      (node (ref "R131") (pin "1") (pinfunction "1_1") (pintype "passive"))
      (node (ref "U104") (pin "6") (pinfunction "IN2-_6") (pintype "passive"))
      (node (ref "U104") (pin "7") (pinfunction "OUT2_7") (pintype "passive"))
    )
    (net (code "29") (name "/V_PANL") (class "Default")
      (node (ref "R127") (pin "1") (pinfunction "1_1") (pintype "passive"))
      (node (ref "XH100") (pin "1") (pinfunction "1_1") (pintype "passive"))
    )
    (net (code "30") (name "/V_PANL_BUF") (class "Default")
      (node (ref "R130") (pin "1") (pinfunction "1_1") (pintype "passive"))
      (node (ref "U104") (pin "1") (pinfunction "OUT1_1") (pintype "passive"))
      (node (ref "U104") (pin "2") (pinfunction "IN1-_2") (pintype "passive"))
    )
    (net (code "31") (name "3V3") (class "Default")
      (node (ref "C108") (pin "2") (pinfunction "2_2") (pintype "passive"))
      (node (ref "C109") (pin "2") (pinfunction "2_2") (pintype "passive"))
      (node (ref "C110") (pin "2") (pinfunction "2_2") (pintype "passive"))
      (node (ref "C116") (pin "2") (pinfunction "2_2") (pintype "passive"))
      (node (ref "C117") (pin "2") (pinfunction "2_2") (pintype "passive"))
      (node (ref "C118") (pin "2") (pinfunction "2_2") (pintype "passive"))
      (node (ref "C121") (pin "2") (pinfunction "2_2") (pintype "passive"))
      (node (ref "FB100") (pin "1") (pinfunction "1_1") (pintype "passive"))
      (node (ref "H100") (pin "5") (pinfunction "5_5") (pintype "passive"))
      (node (ref "H101") (pin "1") (pinfunction "1_1") (pintype "passive"))
      (node (ref "L100") (pin "A") (pinfunction "A_A") (pintype "passive"))
      (node (ref "R100") (pin "2") (pinfunction "2_2") (pintype "passive"))
      (node (ref "R108") (pin "2") (pinfunction "2_2") (pintype "passive"))
      (node (ref "R109") (pin "2") (pinfunction "2_2") (pintype "passive"))
      (node (ref "R119") (pin "2") (pinfunction "2_2") (pintype "passive"))
      (node (ref "R120") (pin "2") (pinfunction "2_2") (pintype "passive"))
      (node (ref "R137") (pin "2") (pinfunction "2_2") (pintype "passive"))
      (node (ref "R140") (pin "1") (pinfunction "1_1") (pintype "passive"))
      (node (ref "U100") (pin "15") (pinfunction "VCC_15") (pintype "passive"))
      (node (ref "U101") (pin "11") (pinfunction "VDDA_11") (pintype "passive"))
      (node (ref "U102") (pin "8") (pinfunction "VCC_8") (pintype "passive"))
      (node (ref "U103") (pin "8") (pinfunction "+_8") (pintype "passive"))
      (node (ref "U104") (pin "8") (pinfunction "+_8") (pintype "passive"))
      (node (ref "U105") (pin "8") (pinfunction "+_8") (pintype "passive"))
    )
    (net (code "32") (name "GND") (class "Default")
      (node (ref "C100") (pin "1") (pinfunction "1_1") (pintype "passive"))
      (node (ref "C101") (pin "1") (pinfunction "1_1") (pintype "passive"))
      (node (ref "C102") (pin "1") (pinfunction "1_1") (pintype "passive"))
      (node (ref "C103") (pin "1") (pinfunction "1_1") (pintype "passive"))
      (node (ref "C104") (pin "1") (pinfunction "1_1") (pintype "passive"))
      (node (ref "C105") (pin "1") (pinfunction "1_1") (pintype "passive"))
      (node (ref "C106") (pin "2") (pinfunction "2_2") (pintype "passive"))
      (node (ref "C107") (pin "2") (pinfunction "2_2") (pintype "passive"))
      (node (ref "C108") (pin "1") (pinfunction "1_1") (pintype "passive"))
      (node (ref "C109") (pin "1") (pinfunction "1_1") (pintype "passive"))
      (node (ref "C110") (pin "1") (pinfunction "1_1") (pintype "passive"))
      (node (ref "C111") (pin "1") (pinfunction "1_1") (pintype "passive"))
      (node (ref "C112") (pin "1") (pinfunction "1_1") (pintype "passive"))
      (node (ref "C113") (pin "1") (pinfunction "1_1") (pintype "passive"))
      (node (ref "C114") (pin "1") (pinfunction "1_1") (pintype "passive"))
      (node (ref "C115") (pin "1") (pinfunction "1_1") (pintype "passive"))
      (node (ref "C116") (pin "1") (pinfunction "1_1") (pintype "passive"))
      (node (ref "C117") (pin "1") (pinfunction "1_1") (pintype "passive"))
      (node (ref "C118") (pin "1") (pinfunction "1_1") (pintype "passive"))
      (node (ref "C121") (pin "1") (pinfunction "1_1") (pintype "passive"))
      (node (ref "C122") (pin "1") (pinfunction "1_1") (pintype "passive"))
      (node (ref "C123") (pin "1") (pinfunction "1_1") (pintype "passive"))
      (node (ref "D-SUB100") (pin "5") (pinfunction "5_5") (pintype "passive"))
      (node (ref "D-SUB100") (pin "SH1") (pinfunction "SHIELD_SH1") (pintype "passive"))
      (node (ref "D-SUB100") (pin "SH2") (pinfunction "SHIELD_SH2") (pintype "passive"))
      (node (ref "H100") (pin "10") (pinfunction "10_10") (pintype "passive"))
      (node (ref "H100") (pin "12") (pinfunction "12_12") (pintype "passive"))
      (node (ref "H100") (pin "4") (pinfunction "4_4") (pintype "passive"))
      (node (ref "H100") (pin "6") (pinfunction "6_6") (pintype "passive"))
      (node (ref "H100") (pin "8") (pinfunction "8_8") (pintype "passive"))
      (node (ref "H101") (pin "4") (pinfunction "4_4") (pintype "passive"))
      (node (ref "H103") (pin "2") (pinfunction "2_2") (pintype "passive"))
      (node (ref "R101") (pin "1") (pinfunction "1_1") (pintype "passive"))
      (node (ref "R121") (pin "1") (pinfunction "1_1") (pintype "passive"))
      (node (ref "R122") (pin "1") (pinfunction "1_1") (pintype "passive"))
      (node (ref "R138") (pin "2") (pinfunction "2_2") (pintype "passive"))
      (node (ref "R139") (pin "2") (pinfunction "2_2") (pintype "passive"))
      (node (ref "R141") (pin "2") (pinfunction "2_2") (pintype "passive"))
      (node (ref "TVS100") (pin "2") (pinfunction "A_2") (pintype "passive"))
      (node (ref "TVS101") (pin "2") (pinfunction "A_2") (pintype "passive"))
      (node (ref "TVS102") (pin "2") (pinfunction "A_2") (pintype "passive"))
      (node (ref "TVS103") (pin "2") (pinfunction "A_2") (pintype "passive"))
      (node (ref "TVS104") (pin "2") (pinfunction "A_2") (pintype "passive"))
      (node (ref "TVS105") (pin "2") (pinfunction "A_2") (pintype "passive"))
      (node (ref "TVS106") (pin "2") (pinfunction "A_2") (pintype "passive"))
      (node (ref "TVS107") (pin "2") (pinfunction "A_2") (pintype "passive"))
      (node (ref "TVS108") (pin "2") (pinfunction "A_2") (pintype "passive"))
      (node (ref "TVS109") (pin "2") (pinfunction "A_2") (pintype "passive"))
      (node (ref "TVS110") (pin "2") (pinfunction "A_2") (pintype "passive"))
      (node (ref "TVS111") (pin "2") (pinfunction "A_2") (pintype "passive"))
      (node (ref "TVS112") (pin "2") (pinfunction "A_2") (pintype "passive"))
      (node (ref "TVS113") (pin "2") (pinfunction "A_2") (pintype "passive"))
      (node (ref "U100") (pin "14") (pinfunction "GND_14") (pintype "passive"))
      (node (ref "U101") (pin "12") (pinfunction "VSSA/VREFLO_12") (pintype "passive"))
      (node (ref "U101") (pin "33") (pinfunction "VSS_33") (pintype "passive"))
      (node (ref "U101") (pin "34") (pinfunction "~{VREGENZ}_34") (pintype "passive"))
      (node (ref "U101") (pin "44") (pinfunction "VSS_44") (pintype "passive"))
      (node (ref "U102") (pin "4") (pinfunction "GND_4") (pintype "passive"))
      (node (ref "U102") (pin "7") (pinfunction "WP_7") (pintype "passive"))
      (node (ref "U103") (pin "4") (pinfunction "-_4") (pintype "passive"))
      (node (ref "U104") (pin "4") (pinfunction "-_4") (pintype "passive"))
      (node (ref "U105") (pin "4") (pinfunction "-_4") (pintype "passive"))
    )
    (net (code "33") (name "Net-(L100-PadC)") (class "Default")
      (node (ref "L100") (pin "C") (pinfunction "C_C") (pintype "passive"))
      (node (ref "R143") (pin "1") (pinfunction "1_1") (pintype "passive"))
    )
    (net (code "34") (name "Net-(U100-C1+)") (class "Default")
      (node (ref "C119") (pin "1") (pinfunction "1_1") (pintype "passive"))
      (node (ref "U100") (pin "2") (pinfunction "C1+_2") (pintype "passive"))
    )
    (net (code "35") (name "Net-(U100-C1-)") (class "Default")
      (node (ref "C119") (pin "2") (pinfunction "2_2") (pintype "passive"))
      (node (ref "U100") (pin "4") (pinfunction "C1-_4") (pintype "passive"))
    )
    (net (code "36") (name "Net-(U100-C2+)") (class "Default")
      (node (ref "C120") (pin "1") (pinfunction "1_1") (pintype "passive"))
      (node (ref "U100") (pin "5") (pinfunction "C2+_5") (pintype "passive"))
    )
    (net (code "37") (name "Net-(U100-C2-)") (class "Default")
      (node (ref "C120") (pin "2") (pinfunction "2_2") (pintype "passive"))
      (node (ref "U100") (pin "6") (pinfunction "C2-_6") (pintype "passive"))
    )
    (net (code "38") (name "Net-(U100-FORCEON)") (class "Default")
      (node (ref "R138") (pin "1") (pinfunction "1_1") (pintype "passive"))
      (node (ref "R140") (pin "2") (pinfunction "2_2") (pintype "passive"))
      (node (ref "U100") (pin "12") (pinfunction "FORCEON_12") (pintype "passive"))
    )
    (net (code "39") (name "Net-(U100-V+)") (class "Default")
      (node (ref "C122") (pin "2") (pinfunction "2_2") (pintype "passive"))
      (node (ref "C123") (pin "2") (pinfunction "2_2") (pintype "passive"))
      (node (ref "U100") (pin "3") (pinfunction "V+_3") (pintype "passive"))
      (node (ref "U100") (pin "7") (pinfunction "V-_7") (pintype "passive"))
    )
    (net (code "40") (name "Net-(U100-~{EN})") (class "Default")
      (node (ref "R141") (pin "1") (pinfunction "1_1") (pintype "passive"))
      (node (ref "U100") (pin "1") (pinfunction "~{EN}_1") (pintype "passive"))
    )
    (net (code "41") (name "Net-(U100-~{FORCEOFF})") (class "Default")
      (node (ref "R137") (pin "1") (pinfunction "1_1") (pintype "passive"))
      (node (ref "R139") (pin "1") (pinfunction "1_1") (pintype "passive"))
      (node (ref "U100") (pin "16") (pinfunction "~{FORCEOFF}_16") (pintype "passive"))
    )
    (net (code "42") (name "Net-(U101-ADCINA0{slash}VREFHI)") (class "Default")
      (node (ref "R128") (pin "2") (pinfunction "2_2") (pintype "passive"))
      (node (ref "U101") (pin "10") (pinfunction "ADCINA0/VREFHI_10") (pintype "passive"))
    )
    (net (code "43") (name "Net-(U101-ADCINA1)") (class "Default")
      (node (ref "R129") (pin "2") (pinfunction "2_2") (pintype "passive"))
      (node (ref "U101") (pin "8") (pinfunction "ADCINA1_8") (pintype "passive"))
    )
    (net (code "44") (name "Net-(U101-ADCINA2{slash}COMP1A{slash}AIO2)") (class "Default")
      (node (ref "R130") (pin "2") (pinfunction "2_2") (pintype "passive"))
      (node (ref "U101") (pin "9") (pinfunction "ADCINA2/COMP1A/AIO2_9") (pintype "passive"))
    )
    (net (code "45") (name "Net-(U101-ADCINA3)") (class "Default")
      (node (ref "R131") (pin "2") (pinfunction "2_2") (pintype "passive"))
      (node (ref "U101") (pin "7") (pinfunction "ADCINA3_7") (pintype "passive"))
    )
    (net (code "46") (name "Net-(U101-ADCINA4{slash}COMP2A{slash}AIO4)") (class "Default")
      (node (ref "R132") (pin "2") (pinfunction "2_2") (pintype "passive"))
      (node (ref "U101") (pin "5") (pinfunction "ADCINA4/COMP2A/AIO4_5") (pintype "passive"))
    )
    (net (code "47") (name "Net-(U101-ADCINA6{slash}AIO6)") (class "Default")
      (node (ref "R133") (pin "2") (pinfunction "2_2") (pintype "passive"))
      (node (ref "U101") (pin "4") (pinfunction "ADCINA6/AIO6_4") (pintype "passive"))
    )
    (net (code "48") (name "Net-(U101-ADCINA7)") (class "Default")
      (node (ref "R134") (pin "2") (pinfunction "2_2") (pintype "passive"))
      (node (ref "U101") (pin "6") (pinfunction "ADCINA7_6") (pintype "passive"))
    )
    (net (code "49") (name "Net-(U101-ADCINB6{slash}AIO14)") (class "Default")
      (node (ref "R143") (pin "2") (pinfunction "2_2") (pintype "passive"))
      (node (ref "U101") (pin "17") (pinfunction "ADCINB6/AIO14_17") (pintype "passive"))
    )
    (net (code "50") (name "Net-(U101-GPIO0{slash}EPWM1A)") (class "Default")
      (node (ref "R117") (pin "1") (pinfunction "1_1") (pintype "passive"))
      (node (ref "U101") (pin "29") (pinfunction "GPIO0/EPWM1A_29") (pintype "passive"))
    )
    (net (code "51") (name "Net-(U101-GPIO1{slash}EPWM1B{slash}COMP1OUT)") (class "Default")
      (node (ref "R142") (pin "1") (pinfunction "1_1") (pintype "passive"))
      (node (ref "U101") (pin "28") (pinfunction "GPIO1/EPWM1B/COMP1OUT_28") (pintype "passive"))
    )
    (net (code "52") (name "Net-(U101-GPIO2{slash}EPWM2A)") (class "Default")
      (node (ref "R118") (pin "1") (pinfunction "1_1") (pintype "passive"))
      (node (ref "U101") (pin "37") (pinfunction "GPIO2/EPWM2A_37") (pintype "passive"))
    )
    (net (code "53") (name "Net-(U101-GPIO12{slash}~{TZ1}{slash}SCITXDA)") (class "Default")
      (node (ref "R146") (pin "1") (pinfunction "1_1") (pintype "passive"))
      (node (ref "U101") (pin "47") (pinfunction "GPIO12/~{TZ1}/SCITXDA_47") (pintype "passive"))
    )
    (net (code "54") (name "Net-(U101-GPIO16{slash}SPISIMOA{slash}~{TZ2})") (class "Default")
      (node (ref "R144") (pin "1") (pinfunction "1_1") (pintype "passive"))
      (node (ref "U101") (pin "27") (pinfunction "GPIO16/SPISIMOA/~{TZ2}_27") (pintype "passive"))
    )
    (net (code "55") (name "Net-(U101-GPIO17{slash}SPISOMIA{slash}~{TZ3})") (class "Default")
      (node (ref "R145") (pin "1") (pinfunction "1_1") (pintype "passive"))
      (node (ref "U101") (pin "26") (pinfunction "GPIO17/SPISOMIA/~{TZ3}_26") (pintype "passive"))
    )
    (net (code "56") (name "Net-(U101-GPIO28{slash}SCIRXDA{slash}SDAA{slash}~{TZ2})") (class "Default")
      (node (ref "R135") (pin "1") (pinfunction "1_1") (pintype "passive"))
      (node (ref "U101") (pin "48") (pinfunction "GPIO28/SCIRXDA/SDAA/~{TZ2}_48") (pintype "passive"))
    )
    (net (code "57") (name "Net-(U101-GPIO29{slash}SCITXDA{slash}SCLA{slash}~{TZ3})") (class "Default")
      (node (ref "R136") (pin "1") (pinfunction "1_1") (pintype "passive"))
      (node (ref "U101") (pin "1") (pinfunction "GPIO29/SCITXDA/SCLA/~{TZ3}_1") (pintype "passive"))
    )
    (net (code "58") (name "Net-(U101-GPIO32{slash}SDAA{slash}EPWMSYNCI{slash}~{ADCSOCAO})") (class "Default")
      (node (ref "R106") (pin "1") (pinfunction "1_1") (pintype "passive"))
      (node (ref "R114") (pin "1") (pinfunction "1_1") (pintype "passive"))
      (node (ref "U101") (pin "31") (pinfunction "GPIO32/SDAA/EPWMSYNCI/~{ADCSOCAO}_31") (pintype "passive"))
    )
    (net (code "59") (name "Net-(U101-GPIO33{slash}SCLA{slash}EPWMSYNCO{slash}~{ADCSOCBO})") (class "Default")
      (node (ref "R107") (pin "1") (pinfunction "1_1") (pintype "passive"))
      (node (ref "R115") (pin "1") (pinfunction "1_1") (pintype "passive"))
      (node (ref "U101") (pin "36") (pinfunction "GPIO33/SCLA/EPWMSYNCO/~{ADCSOCBO}_36") (pintype "passive"))
    )
    (net (code "60") (name "Net-(U101-GPIO35{slash}TDI)") (class "Default")
      (node (ref "R105") (pin "1") (pinfunction "1_1") (pintype "passive"))
      (node (ref "R113") (pin "1") (pinfunction "1_1") (pintype "passive"))
      (node (ref "U101") (pin "20") (pinfunction "GPIO35/TDI_20") (pintype "passive"))
    )
    (net (code "61") (name "Net-(U101-GPIO36{slash}TMS)") (class "Default")
      (node (ref "R104") (pin "1") (pinfunction "1_1") (pintype "passive"))
      (node (ref "R112") (pin "1") (pinfunction "1_1") (pintype "passive"))
      (node (ref "U101") (pin "21") (pinfunction "GPIO36/TMS_21") (pintype "passive"))
    )
    (net (code "62") (name "Net-(U101-GPIO37{slash}TDO)") (class "Default")
      (node (ref "R103") (pin "1") (pinfunction "1_1") (pintype "passive"))
      (node (ref "R111") (pin "1") (pinfunction "1_1") (pintype "passive"))
      (node (ref "U101") (pin "22") (pinfunction "GPIO37/TDO_22") (pintype "passive"))
    )
    (net (code "63") (name "Net-(U101-GPIO38{slash}TCK{slash}XCLKIN)") (class "Default")
      (node (ref "R102") (pin "1") (pinfunction "1_1") (pintype "passive"))
      (node (ref "R110") (pin "1") (pinfunction "1_1") (pintype "passive"))
      (node (ref "U101") (pin "23") (pinfunction "GPIO38/TCK/XCLKIN_23") (pintype "passive"))
    )
    (net (code "64") (name "Net-(U101-VDDIO)") (class "Default")
      (node (ref "C100") (pin "2") (pinfunction "2_2") (pintype "passive"))
      (node (ref "C101") (pin "2") (pinfunction "2_2") (pintype "passive"))
      (node (ref "C102") (pin "2") (pinfunction "2_2") (pintype "passive"))
      (node (ref "C103") (pin "2") (pinfunction "2_2") (pintype "passive"))
      (node (ref "C104") (pin "2") (pinfunction "2_2") (pintype "passive"))
      (node (ref "C105") (pin "2") (pinfunction "2_2") (pintype "passive"))
      (node (ref "FB100") (pin "2") (pinfunction "2_2") (pintype "passive"))
      (node (ref "R102") (pin "2") (pinfunction "2_2") (pintype "passive"))
      (node (ref "R103") (pin "2") (pinfunction "2_2") (pintype "passive"))
      (node (ref "R104") (pin "2") (pinfunction "2_2") (pintype "passive"))
      (node (ref "R105") (pin "2") (pinfunction "2_2") (pintype "passive"))
      (node (ref "R106") (pin "2") (pinfunction "2_2") (pintype "passive"))
      (node (ref "R107") (pin "2") (pinfunction "2_2") (pintype "passive"))
      (node (ref "U101") (pin "32") (pinfunction "VDD_32") (pintype "passive"))
      (node (ref "U101") (pin "35") (pinfunction "VDDIO_35") (pintype "passive"))
      (node (ref "U101") (pin "43") (pinfunction "VDD_43") (pintype "passive"))
    )
    (net (code "65") (name "Net-(U101-X1)") (class "Default")
      (node (ref "C106") (pin "1") (pinfunction "1_1") (pintype "passive"))
      (node (ref "U101") (pin "45") (pinfunction "X1_45") (pintype "passive"))
      (node (ref "Y100") (pin "2") (pinfunction "2_2") (pintype "passive"))
    )
    (net (code "66") (name "Net-(U101-X2)") (class "Default")
      (node (ref "C107") (pin "1") (pinfunction "1_1") (pintype "passive"))
      (node (ref "U101") (pin "46") (pinfunction "X2_46") (pintype "passive"))
      (node (ref "Y100") (pin "1") (pinfunction "1_1") (pintype "passive"))
    )
    (net (code "67") (name "Net-(U101-~{TRST})") (class "Default")
      (node (ref "R101") (pin "2") (pinfunction "2_2") (pintype "passive"))
      (node (ref "R116") (pin "1") (pinfunction "1_1") (pintype "passive"))
      (node (ref "U101") (pin "2") (pinfunction "~{TRST}_2") (pintype "passive"))
    )
    (net (code "68") (name "Net-(U101-~{XRS})") (class "Default")
      (node (ref "R100") (pin "1") (pinfunction "1_1") (pintype "passive"))
      (node (ref "U101") (pin "3") (pinfunction "~{XRS}_3") (pintype "passive"))
    )
    (net (code "69") (name "Net-(U102-A1)") (class "Default")
      (node (ref "R120") (pin "1") (pinfunction "1_1") (pintype "passive"))
      (node (ref "R122") (pin "2") (pinfunction "2_2") (pintype "passive"))
      (node (ref "U102") (pin "2") (pinfunction "A1_2") (pintype "passive"))
    )
    (net (code "70") (name "Net-(U102-A2)") (class "Default")
      (node (ref "R119") (pin "1") (pinfunction "1_1") (pintype "passive"))
      (node (ref "R121") (pin "2") (pinfunction "2_2") (pintype "passive"))
      (node (ref "U102") (pin "3") (pinfunction "A2_3") (pintype "passive"))
    )
    (net (code "71") (name "Net-(U103A-IN1+)") (class "Default")
      (node (ref "C111") (pin "2") (pinfunction "2_2") (pintype "passive"))
      (node (ref "R123") (pin "2") (pinfunction "2_2") (pintype "passive"))
      (node (ref "U103") (pin "3") (pinfunction "IN1+_3") (pintype "passive"))
    )
    (net (code "72") (name "Net-(U103B-IN2+)") (class "Default")
      (node (ref "C112") (pin "2") (pinfunction "2_2") (pintype "passive"))
      (node (ref "R124") (pin "2") (pinfunction "2_2") (pintype "passive"))
      (node (ref "U103") (pin "5") (pinfunction "IN2+_5") (pintype "passive"))
    )
    (net (code "73") (name "Net-(U104A-IN1+)") (class "Default")
      (node (ref "C114") (pin "2") (pinfunction "2_2") (pintype "passive"))
      (node (ref "R127") (pin "2") (pinfunction "2_2") (pintype "passive"))
      (node (ref "U104") (pin "3") (pinfunction "IN1+_3") (pintype "passive"))
    )
    (net (code "74") (name "Net-(U104B-IN2+)") (class "Default")
      (node (ref "C115") (pin "2") (pinfunction "2_2") (pintype "passive"))
      (node (ref "R126") (pin "2") (pinfunction "2_2") (pintype "passive"))
      (node (ref "U104") (pin "5") (pinfunction "IN2+_5") (pintype "passive"))
    )
    (net (code "75") (name "Net-(U105A-IN1+)") (class "Default")
      (node (ref "C113") (pin "2") (pinfunction "2_2") (pintype "passive"))
      (node (ref "R125") (pin "2") (pinfunction "2_2") (pintype "passive"))
      (node (ref "U105") (pin "3") (pinfunction "IN1+_3") (pintype "passive"))
    )
    (net (code "76") (name "unconnected-(D-SUB100-Pad1)") (class "Default")
      (node (ref "D-SUB100") (pin "1") (pinfunction "1_1") (pintype "passive+no_connect"))
    )
    (net (code "77") (name "unconnected-(D-SUB100-Pad4)") (class "Default")
      (node (ref "D-SUB100") (pin "4") (pinfunction "4_4") (pintype "passive+no_connect"))
    )
    (net (code "78") (name "unconnected-(D-SUB100-Pad6)") (class "Default")
      (node (ref "D-SUB100") (pin "6") (pinfunction "6_6") (pintype "passive+no_connect"))
    )
    (net (code "79") (name "unconnected-(D-SUB100-Pad7)") (class "Default")
      (node (ref "D-SUB100") (pin "7") (pinfunction "7_7") (pintype "passive+no_connect"))
    )
    (net (code "80") (name "unconnected-(D-SUB100-Pad8)") (class "Default")
      (node (ref "D-SUB100") (pin "8") (pinfunction "8_8") (pintype "passive+no_connect"))
    )
    (net (code "81") (name "unconnected-(D-SUB100-Pad9)") (class "Default")
      (node (ref "D-SUB100") (pin "9") (pinfunction "9_9") (pintype "passive+no_connect"))
    )
    (net (code "82") (name "unconnected-(R128-Pad1)") (class "Default")
      (node (ref "R128") (pin "1") (pinfunction "1_1") (pintype "passive"))
    )
    (net (code "83") (name "unconnected-(U101-ADCINB1-Pad13)") (class "Default")
      (node (ref "U101") (pin "13") (pinfunction "ADCINB1_13") (pintype "passive"))
    )
    (net (code "84") (name "unconnected-(U101-ADCINB2{slash}COMP1B{slash}AIO10-Pad14)") (class "Default")
      (node (ref "U101") (pin "14") (pinfunction "ADCINB2/COMP1B/AIO10_14") (pintype "passive"))
    )
    (net (code "85") (name "unconnected-(U101-ADCINB3-Pad15)") (class "Default")
      (node (ref "U101") (pin "15") (pinfunction "ADCINB3_15") (pintype "passive"))
    )
    (net (code "86") (name "unconnected-(U101-ADCINB4{slash}COMP2B{slash}AIO12-Pad16)") (class "Default")
      (node (ref "U101") (pin "16") (pinfunction "ADCINB4/COMP2B/AIO12_16") (pintype "passive"))
    )
    (net (code "87") (name "unconnected-(U101-ADCINB7-Pad18)") (class "Default")
      (node (ref "U101") (pin "18") (pinfunction "ADCINB7_18") (pintype "passive"))
    )
    (net (code "88") (name "unconnected-(U101-GPIO3{slash}EPWM2B{slash}COMP2OUT-Pad38)") (class "Default")
      (node (ref "U101") (pin "38") (pinfunction "GPIO3/EPWM2B/COMP2OUT_38") (pintype "passive"))
    )
    (net (code "89") (name "unconnected-(U101-GPIO4{slash}EPWM3A-Pad39)") (class "Default")
      (node (ref "U101") (pin "39") (pinfunction "GPIO4/EPWM3A_39") (pintype "passive"))
    )
    (net (code "90") (name "unconnected-(U101-GPIO5{slash}EPWM3B{slash}ECAP1-Pad40)") (class "Default")
      (node (ref "U101") (pin "40") (pinfunction "GPIO5/EPWM3B/ECAP1_40") (pintype "passive"))
    )
    (net (code "91") (name "unconnected-(U101-GPIO6{slash}EPWM4A{slash}EPWMSYNCI{slash}EPWMSYNCO-Pad41)") (class "Default")
      (node (ref "U101") (pin "41") (pinfunction "GPIO6/EPWM4A/EPWMSYNCI/EPWMSYNCO_41") (pintype "passive"))
    )
    (net (code "92") (name "unconnected-(U101-GPIO7{slash}EPWM4B{slash}SCIRXDA-Pad42)") (class "Default")
      (node (ref "U101") (pin "42") (pinfunction "GPIO7/EPWM4B/SCIRXDA_42") (pintype "passive"))
    )
    (net (code "93") (name "unconnected-(U101-GPIO18{slash}SPICLKA{slash}SCITXDA{slash}XCLKOUT-Pad24)") (class "Default")
      (node (ref "U101") (pin "24") (pinfunction "GPIO18/SPICLKA/SCITXDA/XCLKOUT_24") (pintype "passive"))
    )
    (net (code "94") (name "unconnected-(U101-GPIO19{slash}XCLKIN{slash}~{SPISTEA}{slash}SCIRXDA{slash}ECAP1-Pad25)") (class "Default")
      (node (ref "U101") (pin "25") (pinfunction "GPIO19/XCLKIN/~{SPISTEA}/SCIRXDA/ECAP1_25") (pintype "passive"))
    )
    (net (code "95") (name "unconnected-(U101-GPIO34{slash}COMP2OUT-Pad19)") (class "Default")
      (node (ref "U101") (pin "19") (pinfunction "GPIO34/COMP2OUT_19") (pintype "passive"))
    )
    (net (code "96") (name "unconnected-(U101-TEST-Pad30)") (class "Default")
      (node (ref "U101") (pin "30") (pinfunction "TEST_30") (pintype "passive"))
    )
    (net (code "97") (name "unconnected-(U102-NC-Pad1)") (class "Default")
      (node (ref "U102") (pin "1") (pinfunction "NC_1") (pintype "passive+no_connect"))
    )
  )
)
